# BlueSunOFP.net
KiCad netlist of a schematic drawn in EAGLE
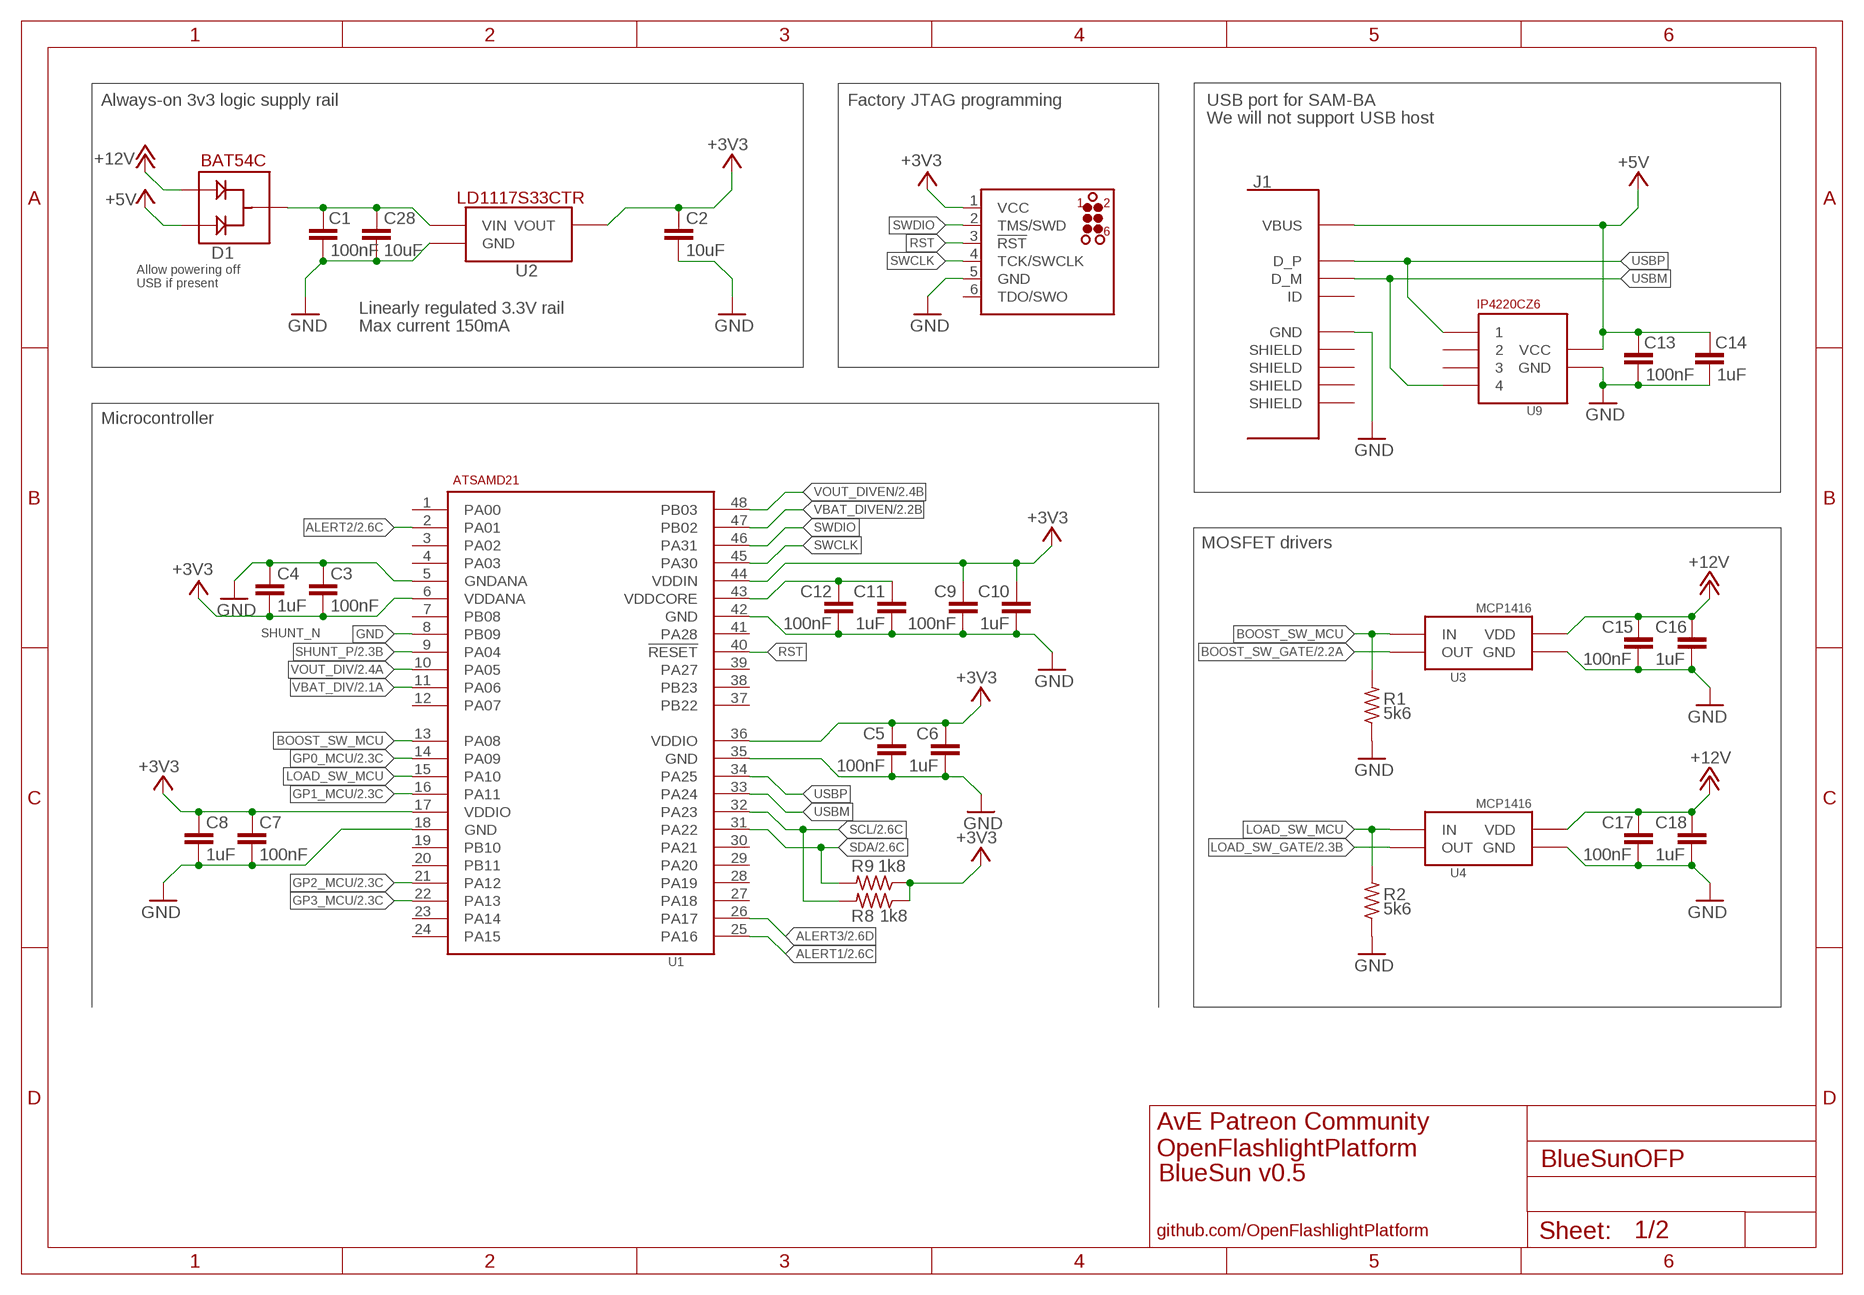
[diagram p0: schematic, sheet 1]
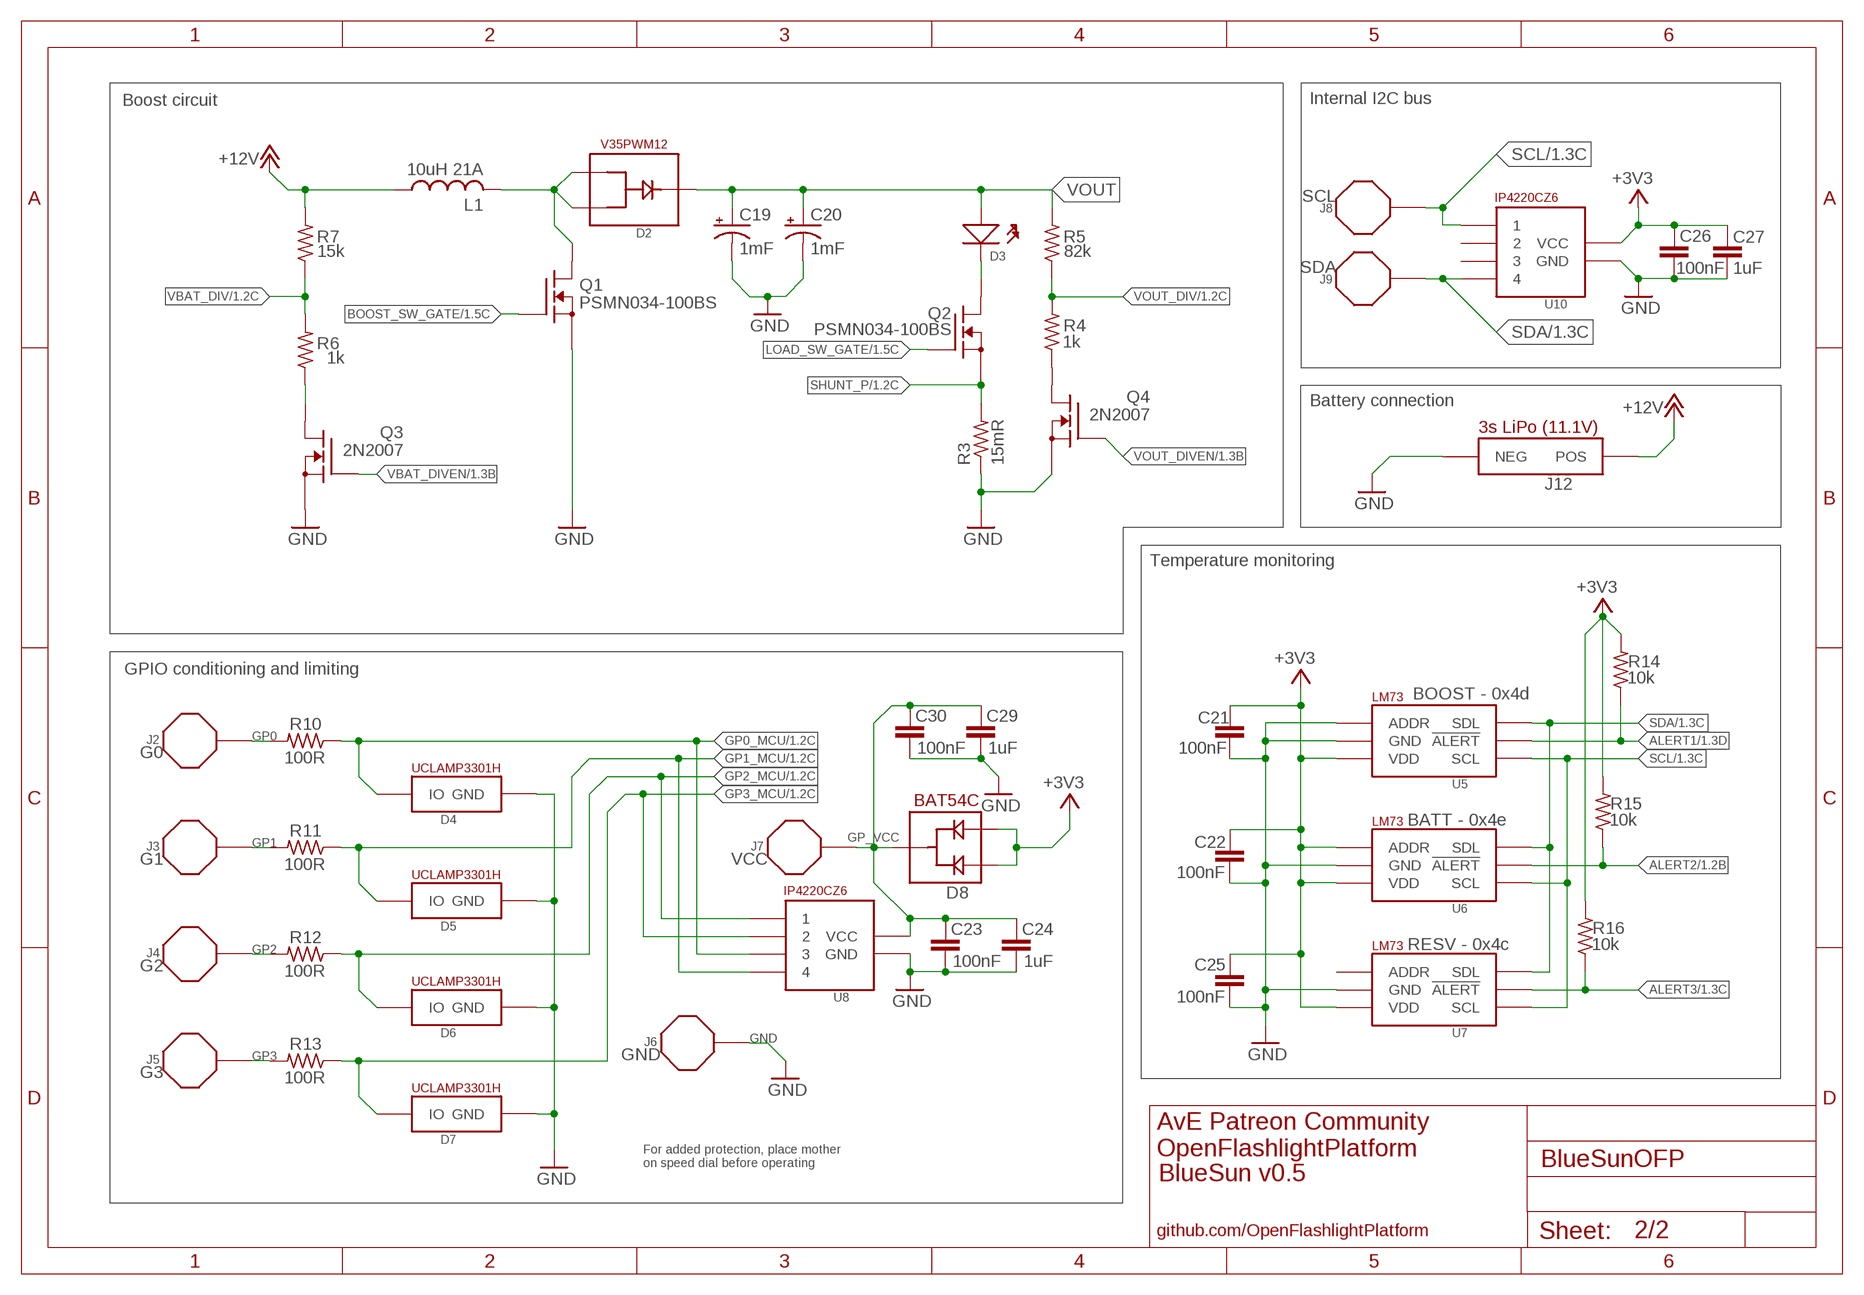
[diagram p1: schematic, sheet 2]

(export (version "E")
  (design (tool "Eeschema 10.0.6"))
  (components
    (comp (ref "C1")
      (value "100nF")
      (footprint "eagle-import:C0603K")
      (libsource (lib "eagle-import") (part "C-EUC0603K"))
    )
    (comp (ref "C2")
      (value "10uF")
      (footprint "eagle-import:C0603K")
      (libsource (lib "eagle-import") (part "C-EUC0603K"))
    )
    (comp (ref "C3")
      (value "100nF")
      (footprint "eagle-import:C0402K")
      (libsource (lib "eagle-import") (part "C-EUC0402K"))
    )
    (comp (ref "C4")
      (value "1uF")
      (footprint "eagle-import:C0402K")
      (libsource (lib "eagle-import") (part "C-EUC0402K"))
    )
    (comp (ref "C5")
      (value "100nF")
      (footprint "eagle-import:C0402K")
      (libsource (lib "eagle-import") (part "C-EUC0402K"))
    )
    (comp (ref "C6")
      (value "1uF")
      (footprint "eagle-import:C0402K")
      (libsource (lib "eagle-import") (part "C-EUC0402K"))
    )
    (comp (ref "C7")
      (value "100nF")
      (footprint "eagle-import:C0402K")
      (libsource (lib "eagle-import") (part "C-EUC0402K"))
    )
    (comp (ref "C8")
      (value "1uF")
      (footprint "eagle-import:C0402K")
      (libsource (lib "eagle-import") (part "C-EUC0402K"))
    )
    (comp (ref "C9")
      (value "100nF")
      (footprint "eagle-import:C0402K")
      (libsource (lib "eagle-import") (part "C-EUC0402K"))
    )
    (comp (ref "C10")
      (value "1uF")
      (footprint "eagle-import:C0402K")
      (libsource (lib "eagle-import") (part "C-EUC0402K"))
    )
    (comp (ref "C11")
      (value "1uF")
      (footprint "eagle-import:C0402K")
      (libsource (lib "eagle-import") (part "C-EUC0402K"))
    )
    (comp (ref "C12")
      (value "100nF")
      (footprint "eagle-import:C0402K")
      (libsource (lib "eagle-import") (part "C-EUC0402K"))
    )
    (comp (ref "C13")
      (value "100nF")
      (footprint "eagle-import:C0603K")
      (libsource (lib "eagle-import") (part "C-EUC0603K"))
    )
    (comp (ref "C14")
      (value "1uF")
      (footprint "eagle-import:C0603K")
      (libsource (lib "eagle-import") (part "C-EUC0603K"))
    )
    (comp (ref "C15")
      (value "100nF")
      (footprint "eagle-import:C0603K")
      (libsource (lib "eagle-import") (part "C-EUC0603K"))
    )
    (comp (ref "C16")
      (value "1uF")
      (footprint "eagle-import:C0603K")
      (libsource (lib "eagle-import") (part "C-EUC0603K"))
    )
    (comp (ref "C17")
      (value "100nF")
      (footprint "eagle-import:C0603K")
      (libsource (lib "eagle-import") (part "C-EUC0603K"))
    )
    (comp (ref "C18")
      (value "1uF")
      (footprint "eagle-import:C0603K")
      (libsource (lib "eagle-import") (part "C-EUC0603K"))
    )
    (comp (ref "C28")
      (value "10uF")
      (footprint "eagle-import:C0603K")
      (libsource (lib "eagle-import") (part "C-EUC0603K"))
    )
    (comp (ref "D1")
      (value "BAT54C")
      (footprint "eagle-import:SOT23")
      (libsource (lib "eagle-import") (part "BAT54C"))
    )
    (comp (ref "J1")
      (value "USBSMT")
      (footprint "eagle-import:USB_SMT")
      (libsource (lib "eagle-import") (part "USBSMT"))
    )
    (comp (ref "R1")
      (value "5k6")
      (footprint "eagle-import:R0603")
      (libsource (lib "eagle-import") (part "R-US_R0603"))
    )
    (comp (ref "R2")
      (value "5k6")
      (footprint "eagle-import:R0603")
      (libsource (lib "eagle-import") (part "R-US_R0603"))
    )
    (comp (ref "R8")
      (value "1k8")
      (footprint "eagle-import:R0603")
      (libsource (lib "eagle-import") (part "R-US_R0603"))
    )
    (comp (ref "R9")
      (value "1k8")
      (footprint "eagle-import:R0603")
      (libsource (lib "eagle-import") (part "R-US_R0603"))
    )
    (comp (ref "U$1")
      (value "JLINK_CONNECT")
      (footprint "eagle-import:TC2030-MCP-NL")
      (libsource (lib "eagle-import") (part "JLINK_CONNECT"))
    )
    (comp (ref "U1")
      (value "SAMD21")
      (footprint "eagle-import:TQFP48")
      (libsource (lib "eagle-import") (part "SAMD21"))
    )
    (comp (ref "U2")
      (value "LD1117S33CTR_3V3_REG")
      (footprint "eagle-import:SOT223")
      (libsource (lib "eagle-import") (part "LD1117S33CTR_3V3_REG"))
    )
    (comp (ref "U3")
      (value "MCP1416")
      (footprint "eagle-import:SOT23-5")
      (libsource (lib "eagle-import") (part "MCP1416"))
    )
    (comp (ref "U4")
      (value "MCP1416")
      (footprint "eagle-import:SOT23-5")
      (libsource (lib "eagle-import") (part "MCP1416"))
    )
    (comp (ref "U9")
      (value "IP4220CZ6")
      (footprint "eagle-import:SOT457")
      (libsource (lib "eagle-import") (part "IP4220CZ6"))
    )
    (comp (ref "C19")
      (value "1mF")
      (footprint "eagle-import:10MMCAP")
      (libsource (lib "eagle-import") (part "10MMCAP"))
    )
    (comp (ref "C20")
      (value "1mF")
      (footprint "eagle-import:10MMCAP")
      (libsource (lib "eagle-import") (part "10MMCAP"))
    )
    (comp (ref "C21")
      (value "100nF")
      (footprint "eagle-import:C0603K")
      (libsource (lib "eagle-import") (part "C-EUC0603K"))
    )
    (comp (ref "C22")
      (value "100nF")
      (footprint "eagle-import:C0603K")
      (libsource (lib "eagle-import") (part "C-EUC0603K"))
    )
    (comp (ref "C23")
      (value "100nF")
      (footprint "eagle-import:C0603K")
      (libsource (lib "eagle-import") (part "C-EUC0603K"))
    )
    (comp (ref "C24")
      (value "1uF")
      (footprint "eagle-import:C0603K")
      (libsource (lib "eagle-import") (part "C-EUC0603K"))
    )
    (comp (ref "C25")
      (value "100nF")
      (footprint "eagle-import:C0603K")
      (libsource (lib "eagle-import") (part "C-EUC0603K"))
    )
    (comp (ref "C26")
      (value "100nF")
      (footprint "eagle-import:C0603K")
      (libsource (lib "eagle-import") (part "C-EUC0603K"))
    )
    (comp (ref "C27")
      (value "1uF")
      (footprint "eagle-import:C0603K")
      (libsource (lib "eagle-import") (part "C-EUC0603K"))
    )
    (comp (ref "C29")
      (value "1uF")
      (footprint "eagle-import:C0603K")
      (libsource (lib "eagle-import") (part "C-EUC0603K"))
    )
    (comp (ref "C30")
      (value "100nF")
      (footprint "eagle-import:C0603K")
      (libsource (lib "eagle-import") (part "C-EUC0603K"))
    )
    (comp (ref "D2")
      (value "DIODE")
      (footprint "eagle-import:SLIMPAK")
      (libsource (lib "eagle-import") (part "DIODE"))
    )
    (comp (ref "D3")
      (value "CREE_COB")
      (footprint "eagle-import:CREE_WIRE_MOUNT")
      (libsource (lib "eagle-import") (part "CREE_COB"))
    )
    (comp (ref "D4")
      (value "UCLAMP3301H")
      (footprint "eagle-import:SOD523")
      (libsource (lib "eagle-import") (part "UCLAMP3301H"))
    )
    (comp (ref "D5")
      (value "UCLAMP3301H")
      (footprint "eagle-import:SOD523")
      (libsource (lib "eagle-import") (part "UCLAMP3301H"))
    )
    (comp (ref "D6")
      (value "UCLAMP3301H")
      (footprint "eagle-import:SOD523")
      (libsource (lib "eagle-import") (part "UCLAMP3301H"))
    )
    (comp (ref "D7")
      (value "UCLAMP3301H")
      (footprint "eagle-import:SOD523")
      (libsource (lib "eagle-import") (part "UCLAMP3301H"))
    )
    (comp (ref "D8")
      (value "BAT54C")
      (footprint "eagle-import:SOT23")
      (libsource (lib "eagle-import") (part "BAT54C"))
    )
    (comp (ref "J2")
      (value "G0")
      (footprint "eagle-import:EXT_PIN")
      (libsource (lib "eagle-import") (part "EXT_PIN"))
    )
    (comp (ref "J3")
      (value "G1")
      (footprint "eagle-import:EXT_PIN")
      (libsource (lib "eagle-import") (part "EXT_PIN"))
    )
    (comp (ref "J4")
      (value "G2")
      (footprint "eagle-import:EXT_PIN")
      (libsource (lib "eagle-import") (part "EXT_PIN"))
    )
    (comp (ref "J5")
      (value "G3")
      (footprint "eagle-import:EXT_PIN")
      (libsource (lib "eagle-import") (part "EXT_PIN"))
    )
    (comp (ref "J6")
      (value "GND")
      (footprint "eagle-import:EXT_PIN")
      (libsource (lib "eagle-import") (part "EXT_PIN"))
    )
    (comp (ref "J7")
      (value "VCC")
      (footprint "eagle-import:EXT_PIN")
      (libsource (lib "eagle-import") (part "EXT_PIN"))
    )
    (comp (ref "J8")
      (value "SCL")
      (footprint "eagle-import:EXT_PIN")
      (libsource (lib "eagle-import") (part "EXT_PIN"))
    )
    (comp (ref "J9")
      (value "SDA")
      (footprint "eagle-import:EXT_PIN")
      (libsource (lib "eagle-import") (part "EXT_PIN"))
    )
    (comp (ref "J12")
      (value "BATTERY")
      (footprint "eagle-import:CREE_WIRE_MOUNT")
      (libsource (lib "eagle-import") (part "BATTERY"))
    )
    (comp (ref "L1")
      (value "10uH 21A")
      (footprint "eagle-import:INDUCTOR")
      (libsource (lib "eagle-import") (part "INDUCTOR"))
    )
    (comp (ref "Q1")
      (value "PSMN034-100BS")
      (footprint "eagle-import:D2PAK")
      (libsource (lib "eagle-import") (part "MOSFET"))
    )
    (comp (ref "Q2")
      (value "PSMN034-100BS")
      (footprint "eagle-import:D2PAK")
      (libsource (lib "eagle-import") (part "MOSFET"))
    )
    (comp (ref "Q3")
      (value "2N2007")
      (footprint "eagle-import:SOT23")
      (libsource (lib "eagle-import") (part "SMALL_MOSFET"))
    )
    (comp (ref "Q4")
      (value "2N2007")
      (footprint "eagle-import:SOT23")
      (libsource (lib "eagle-import") (part "SMALL_MOSFET"))
    )
    (comp (ref "R3")
      (value "15mR")
      (footprint "eagle-import:R2512")
      (libsource (lib "eagle-import") (part "R-US_R2512"))
    )
    (comp (ref "R4")
      (value "1k")
      (footprint "eagle-import:R0603")
      (libsource (lib "eagle-import") (part "R-US_R0603"))
    )
    (comp (ref "R5")
      (value "82k")
      (footprint "eagle-import:R0603")
      (libsource (lib "eagle-import") (part "R-US_R0603"))
    )
    (comp (ref "R6")
      (value "1k")
      (footprint "eagle-import:R0603")
      (libsource (lib "eagle-import") (part "R-US_R0603"))
    )
    (comp (ref "R7")
      (value "15k")
      (footprint "eagle-import:R0603")
      (libsource (lib "eagle-import") (part "R-US_R0603"))
    )
    (comp (ref "R10")
      (value "100R")
      (footprint "eagle-import:R0603")
      (libsource (lib "eagle-import") (part "R-US_R0603"))
    )
    (comp (ref "R11")
      (value "100R")
      (footprint "eagle-import:R0603")
      (libsource (lib "eagle-import") (part "R-US_R0603"))
    )
    (comp (ref "R12")
      (value "100R")
      (footprint "eagle-import:R0603")
      (libsource (lib "eagle-import") (part "R-US_R0603"))
    )
    (comp (ref "R13")
      (value "100R")
      (footprint "eagle-import:R0603")
      (libsource (lib "eagle-import") (part "R-US_R0603"))
    )
    (comp (ref "R14")
      (value "10k")
      (footprint "eagle-import:R0603")
      (libsource (lib "eagle-import") (part "R-US_R0603"))
    )
    (comp (ref "R15")
      (value "10k")
      (footprint "eagle-import:R0603")
      (libsource (lib "eagle-import") (part "R-US_R0603"))
    )
    (comp (ref "R16")
      (value "10k")
      (footprint "eagle-import:R0603")
      (libsource (lib "eagle-import") (part "R-US_R0603"))
    )
    (comp (ref "U5")
      (value "LM73")
      (footprint "eagle-import:SOT23-6")
      (libsource (lib "eagle-import") (part "LM73"))
    )
    (comp (ref "U6")
      (value "LM73")
      (footprint "eagle-import:SOT23-6")
      (libsource (lib "eagle-import") (part "LM73"))
    )
    (comp (ref "U7")
      (value "LM73")
      (footprint "eagle-import:SOT23-6")
      (libsource (lib "eagle-import") (part "LM73"))
    )
    (comp (ref "U8")
      (value "IP4220CZ6")
      (footprint "eagle-import:SOT457")
      (libsource (lib "eagle-import") (part "IP4220CZ6"))
    )
    (comp (ref "U10")
      (value "IP4220CZ6")
      (footprint "eagle-import:SOT457")
      (libsource (lib "eagle-import") (part "IP4220CZ6"))
    )
  )
  (nets
    (net (code "1") (name "+3V3") (class "Default")
      (node (ref "C10") (pin "1") (pinfunction "1_1") (pintype "passive"))
      (node (ref "C2") (pin "1") (pinfunction "1_1") (pintype "passive"))
      (node (ref "C21") (pin "1") (pinfunction "1_1") (pintype "passive"))
      (node (ref "C22") (pin "1") (pinfunction "1_1") (pintype "passive"))
      (node (ref "C25") (pin "1") (pinfunction "1_1") (pintype "passive"))
      (node (ref "C26") (pin "1") (pinfunction "1_1") (pintype "passive"))
      (node (ref "C27") (pin "1") (pinfunction "1_1") (pintype "passive"))
      (node (ref "C3") (pin "2") (pinfunction "2_2") (pintype "passive"))
      (node (ref "C4") (pin "2") (pinfunction "2_2") (pintype "passive"))
      (node (ref "C5") (pin "1") (pinfunction "1_1") (pintype "passive"))
      (node (ref "C6") (pin "1") (pinfunction "1_1") (pintype "passive"))
      (node (ref "C7") (pin "1") (pinfunction "1_1") (pintype "passive"))
      (node (ref "C8") (pin "1") (pinfunction "1_1") (pintype "passive"))
      (node (ref "C9") (pin "1") (pinfunction "1_1") (pintype "passive"))
      (node (ref "D8") (pin "1") (pinfunction "P1_1") (pintype "bidirectional"))
      (node (ref "D8") (pin "2") (pinfunction "P2_2") (pintype "bidirectional"))
      (node (ref "R14") (pin "2") (pinfunction "2_2") (pintype "passive"))
      (node (ref "R15") (pin "2") (pinfunction "2_2") (pintype "passive"))
      (node (ref "R16") (pin "2") (pinfunction "2_2") (pintype "passive"))
      (node (ref "R8") (pin "1") (pinfunction "1_1") (pintype "passive"))
      (node (ref "R9") (pin "1") (pinfunction "1_1") (pintype "passive"))
      (node (ref "U$1") (pin "1") (pinfunction "VCC_1") (pintype "passive"))
      (node (ref "U1") (pin "17") (pinfunction "VDDIO_17") (pintype "bidirectional"))
      (node (ref "U1") (pin "36") (pinfunction "VDDIO_36") (pintype "bidirectional"))
      (node (ref "U1") (pin "44") (pinfunction "VDDIN_44") (pintype "bidirectional"))
      (node (ref "U1") (pin "6") (pinfunction "VDDANA_6") (pintype "bidirectional"))
      (node (ref "U10") (pin "5") (pinfunction "VCC_5") (pintype "bidirectional"))
      (node (ref "U2") (pin "2") (pinfunction "VOUT_2") (pintype "bidirectional"))
      (node (ref "U5") (pin "3") (pinfunction "VDD_3") (pintype "bidirectional"))
      (node (ref "U6") (pin "1") (pinfunction "ADDR_1") (pintype "bidirectional"))
      (node (ref "U6") (pin "3") (pinfunction "VDD_3") (pintype "bidirectional"))
      (node (ref "U7") (pin "3") (pinfunction "VDD_3") (pintype "bidirectional"))
    )
    (net (code "2") (name "+5V") (class "Default")
      (node (ref "C13") (pin "1") (pinfunction "1_1") (pintype "passive"))
      (node (ref "C14") (pin "1") (pinfunction "1_1") (pintype "passive"))
      (node (ref "D1") (pin "2") (pinfunction "P2_2") (pintype "bidirectional"))
      (node (ref "J1") (pin "1VBUS") (pinfunction "VBUS_1VBUS") (pintype "bidirectional"))
      (node (ref "U9") (pin "5") (pinfunction "VCC_5") (pintype "bidirectional"))
    )
    (net (code "3") (name "+12V") (class "Default")
      (node (ref "C15") (pin "1") (pinfunction "1_1") (pintype "passive"))
      (node (ref "C16") (pin "1") (pinfunction "1_1") (pintype "passive"))
      (node (ref "C17") (pin "1") (pinfunction "1_1") (pintype "passive"))
      (node (ref "C18") (pin "1") (pinfunction "1_1") (pintype "passive"))
      (node (ref "D1") (pin "1") (pinfunction "P1_1") (pintype "bidirectional"))
      (node (ref "J12") (pin "POS") (pinfunction "POS_POS") (pintype "bidirectional"))
      (node (ref "L1") (pin "P$1") (pinfunction "1_P$1") (pintype "passive"))
      (node (ref "R7") (pin "2") (pinfunction "2_2") (pintype "passive"))
      (node (ref "U3") (pin "2") (pinfunction "VDD_2") (pintype "bidirectional"))
      (node (ref "U4") (pin "2") (pinfunction "VDD_2") (pintype "bidirectional"))
    )
    (net (code "4") (name "ALERT1") (class "Default")
      (node (ref "R14") (pin "1") (pinfunction "1_1") (pintype "passive"))
      (node (ref "U1") (pin "25") (pinfunction "PA16_25") (pintype "bidirectional"))
      (node (ref "U5") (pin "5") (pinfunction "~{ALERT}_5") (pintype "bidirectional"))
    )
    (net (code "5") (name "ALERT2") (class "Default")
      (node (ref "R15") (pin "1") (pinfunction "1_1") (pintype "passive"))
      (node (ref "U1") (pin "2") (pinfunction "PA01_2") (pintype "bidirectional"))
      (node (ref "U6") (pin "5") (pinfunction "~{ALERT}_5") (pintype "bidirectional"))
    )
    (net (code "6") (name "ALERT3") (class "Default")
      (node (ref "R16") (pin "1") (pinfunction "1_1") (pintype "passive"))
      (node (ref "U1") (pin "26") (pinfunction "PA17_26") (pintype "bidirectional"))
      (node (ref "U7") (pin "5") (pinfunction "~{ALERT}_5") (pintype "bidirectional"))
    )
    (net (code "7") (name "BOOST_SW_GATE") (class "Default")
      (node (ref "Q1") (pin "1") (pinfunction "G_1") (pintype "passive"))
      (node (ref "U3") (pin "5") (pinfunction "OUT_5") (pintype "bidirectional"))
    )
    (net (code "8") (name "BOOST_SW_MCU") (class "Default")
      (node (ref "R1") (pin "2") (pinfunction "2_2") (pintype "passive"))
      (node (ref "U1") (pin "13") (pinfunction "PA08_13") (pintype "bidirectional"))
      (node (ref "U3") (pin "3") (pinfunction "IN_3") (pintype "bidirectional"))
    )
    (net (code "9") (name "GND") (class "Default")
      (node (ref "C1") (pin "2") (pinfunction "2_2") (pintype "passive"))
      (node (ref "C10") (pin "2") (pinfunction "2_2") (pintype "passive"))
      (node (ref "C11") (pin "2") (pinfunction "2_2") (pintype "passive"))
      (node (ref "C12") (pin "2") (pinfunction "2_2") (pintype "passive"))
      (node (ref "C13") (pin "2") (pinfunction "2_2") (pintype "passive"))
      (node (ref "C14") (pin "2") (pinfunction "2_2") (pintype "passive"))
      (node (ref "C15") (pin "2") (pinfunction "2_2") (pintype "passive"))
      (node (ref "C16") (pin "2") (pinfunction "2_2") (pintype "passive"))
      (node (ref "C17") (pin "2") (pinfunction "2_2") (pintype "passive"))
      (node (ref "C18") (pin "2") (pinfunction "2_2") (pintype "passive"))
      (node (ref "C19") (pin "NEG") (pinfunction "-_NEG") (pintype "passive"))
      (node (ref "C2") (pin "2") (pinfunction "2_2") (pintype "passive"))
      (node (ref "C20") (pin "NEG") (pinfunction "-_NEG") (pintype "passive"))
      (node (ref "C21") (pin "2") (pinfunction "2_2") (pintype "passive"))
      (node (ref "C22") (pin "2") (pinfunction "2_2") (pintype "passive"))
      (node (ref "C23") (pin "2") (pinfunction "2_2") (pintype "passive"))
      (node (ref "C24") (pin "2") (pinfunction "2_2") (pintype "passive"))
      (node (ref "C25") (pin "2") (pinfunction "2_2") (pintype "passive"))
      (node (ref "C26") (pin "2") (pinfunction "2_2") (pintype "passive"))
      (node (ref "C27") (pin "2") (pinfunction "2_2") (pintype "passive"))
      (node (ref "C28") (pin "2") (pinfunction "2_2") (pintype "passive"))
      (node (ref "C29") (pin "2") (pinfunction "2_2") (pintype "passive"))
      (node (ref "C3") (pin "1") (pinfunction "1_1") (pintype "passive"))
      (node (ref "C30") (pin "2") (pinfunction "2_2") (pintype "passive"))
      (node (ref "C4") (pin "1") (pinfunction "1_1") (pintype "passive"))
      (node (ref "C5") (pin "2") (pinfunction "2_2") (pintype "passive"))
      (node (ref "C6") (pin "2") (pinfunction "2_2") (pintype "passive"))
      (node (ref "C7") (pin "2") (pinfunction "2_2") (pintype "passive"))
      (node (ref "C8") (pin "2") (pinfunction "2_2") (pintype "passive"))
      (node (ref "C9") (pin "2") (pinfunction "2_2") (pintype "passive"))
      (node (ref "D4") (pin "NOLINE") (pinfunction "GND_NOLINE") (pintype "bidirectional"))
      (node (ref "D5") (pin "NOLINE") (pinfunction "GND_NOLINE") (pintype "bidirectional"))
      (node (ref "D6") (pin "NOLINE") (pinfunction "GND_NOLINE") (pintype "bidirectional"))
      (node (ref "D7") (pin "NOLINE") (pinfunction "GND_NOLINE") (pintype "bidirectional"))
      (node (ref "J1") (pin "5GND") (pinfunction "GND_5GND") (pintype "bidirectional"))
      (node (ref "J12") (pin "NEG") (pinfunction "NEG_NEG") (pintype "bidirectional"))
      (node (ref "J6") (pin "P$1") (pinfunction "P$1_P$1") (pintype "bidirectional"))
      (node (ref "Q1") (pin "3") (pinfunction "S_3") (pintype "passive"))
      (node (ref "Q3") (pin "2") (pinfunction "S_2") (pintype "passive"))
      (node (ref "Q4") (pin "2") (pinfunction "S_2") (pintype "passive"))
      (node (ref "R1") (pin "1") (pinfunction "1_1") (pintype "passive"))
      (node (ref "R2") (pin "1") (pinfunction "1_1") (pintype "passive"))
      (node (ref "R3") (pin "1") (pinfunction "1_1") (pintype "passive"))
      (node (ref "U$1") (pin "5") (pinfunction "GND_5") (pintype "power_in"))
      (node (ref "U1") (pin "18") (pinfunction "GND_18") (pintype "bidirectional"))
      (node (ref "U1") (pin "35") (pinfunction "GND_35") (pintype "bidirectional"))
      (node (ref "U1") (pin "42") (pinfunction "GND_42") (pintype "bidirectional"))
      (node (ref "U1") (pin "5") (pinfunction "GNDANA_5") (pintype "bidirectional"))
      (node (ref "U1") (pin "8") (pinfunction "PB09_8") (pintype "bidirectional"))
      (node (ref "U10") (pin "2") (pinfunction "GND_2") (pintype "bidirectional"))
      (node (ref "U2") (pin "1") (pinfunction "GND_1") (pintype "bidirectional"))
      (node (ref "U3") (pin "4") (pinfunction "GND_4") (pintype "bidirectional"))
      (node (ref "U4") (pin "4") (pinfunction "GND_4") (pintype "bidirectional"))
      (node (ref "U5") (pin "1") (pinfunction "ADDR_1") (pintype "bidirectional"))
      (node (ref "U5") (pin "2") (pinfunction "GND_2") (pintype "bidirectional"))
      (node (ref "U6") (pin "2") (pinfunction "GND_2") (pintype "bidirectional"))
      (node (ref "U7") (pin "2") (pinfunction "GND_2") (pintype "bidirectional"))
      (node (ref "U8") (pin "2") (pinfunction "GND_2") (pintype "bidirectional"))
      (node (ref "U9") (pin "2") (pinfunction "GND_2") (pintype "bidirectional"))
    )
    (net (code "10") (name "GP0") (class "Default")
      (node (ref "J2") (pin "P$1") (pinfunction "P$1_P$1") (pintype "bidirectional"))
      (node (ref "R10") (pin "2") (pinfunction "2_2") (pintype "passive"))
    )
    (net (code "11") (name "GP0_MCU") (class "Default")
      (node (ref "D4") (pin "LINE") (pinfunction "IO_LINE") (pintype "bidirectional"))
      (node (ref "R10") (pin "1") (pinfunction "1_1") (pintype "passive"))
      (node (ref "U1") (pin "14") (pinfunction "PA09_14") (pintype "bidirectional"))
      (node (ref "U8") (pin "4") (pinfunction "3_4") (pintype "bidirectional"))
    )
    (net (code "12") (name "GP1") (class "Default")
      (node (ref "J3") (pin "P$1") (pinfunction "P$1_P$1") (pintype "bidirectional"))
      (node (ref "R11") (pin "2") (pinfunction "2_2") (pintype "passive"))
    )
    (net (code "13") (name "GP1_MCU") (class "Default")
      (node (ref "D5") (pin "LINE") (pinfunction "IO_LINE") (pintype "bidirectional"))
      (node (ref "R11") (pin "1") (pinfunction "1_1") (pintype "passive"))
      (node (ref "U1") (pin "16") (pinfunction "PA11_16") (pintype "bidirectional"))
      (node (ref "U8") (pin "6") (pinfunction "4_6") (pintype "bidirectional"))
    )
    (net (code "14") (name "GP2") (class "Default")
      (node (ref "J4") (pin "P$1") (pinfunction "P$1_P$1") (pintype "bidirectional"))
      (node (ref "R12") (pin "2") (pinfunction "2_2") (pintype "passive"))
    )
    (net (code "15") (name "GP2_MCU") (class "Default")
      (node (ref "D6") (pin "LINE") (pinfunction "IO_LINE") (pintype "bidirectional"))
      (node (ref "R12") (pin "1") (pinfunction "1_1") (pintype "passive"))
      (node (ref "U1") (pin "21") (pinfunction "PA12_21") (pintype "bidirectional"))
      (node (ref "U8") (pin "1") (pinfunction "1_1") (pintype "bidirectional"))
    )
    (net (code "16") (name "GP3") (class "Default")
      (node (ref "J5") (pin "P$1") (pinfunction "P$1_P$1") (pintype "bidirectional"))
      (node (ref "R13") (pin "2") (pinfunction "2_2") (pintype "passive"))
    )
    (net (code "17") (name "GP3_MCU") (class "Default")
      (node (ref "D7") (pin "LINE") (pinfunction "IO_LINE") (pintype "bidirectional"))
      (node (ref "R13") (pin "1") (pinfunction "1_1") (pintype "passive"))
      (node (ref "U1") (pin "22") (pinfunction "PA13_22") (pintype "bidirectional"))
      (node (ref "U8") (pin "3") (pinfunction "2_3") (pintype "bidirectional"))
    )
    (net (code "18") (name "GP_VCC") (class "Default")
      (node (ref "C23") (pin "1") (pinfunction "1_1") (pintype "passive"))
      (node (ref "C24") (pin "1") (pinfunction "1_1") (pintype "passive"))
      (node (ref "C29") (pin "1") (pinfunction "1_1") (pintype "passive"))
      (node (ref "C30") (pin "1") (pinfunction "1_1") (pintype "passive"))
      (node (ref "D8") (pin "3") (pinfunction "NEG_3") (pintype "bidirectional"))
      (node (ref "J7") (pin "P$1") (pinfunction "P$1_P$1") (pintype "bidirectional"))
      (node (ref "U8") (pin "5") (pinfunction "VCC_5") (pintype "bidirectional"))
    )
    (net (code "19") (name "LOAD_SW_GATE") (class "Default")
      (node (ref "Q2") (pin "1") (pinfunction "G_1") (pintype "passive"))
      (node (ref "U4") (pin "5") (pinfunction "OUT_5") (pintype "bidirectional"))
    )
    (net (code "20") (name "LOAD_SW_MCU") (class "Default")
      (node (ref "R2") (pin "2") (pinfunction "2_2") (pintype "passive"))
      (node (ref "U1") (pin "15") (pinfunction "PA10_15") (pintype "bidirectional"))
      (node (ref "U4") (pin "3") (pinfunction "IN_3") (pintype "bidirectional"))
    )
    (net (code "21") (name "Net-(D1-NEG)") (class "Default")
      (node (ref "C1") (pin "1") (pinfunction "1_1") (pintype "passive"))
      (node (ref "C28") (pin "1") (pinfunction "1_1") (pintype "passive"))
      (node (ref "D1") (pin "3") (pinfunction "NEG_3") (pintype "bidirectional"))
      (node (ref "U2") (pin "3") (pinfunction "VIN_3") (pintype "bidirectional"))
    )
    (net (code "22") (name "Net-(L1-2)") (class "Default")
      (node (ref "D2") (pin "1") (pinfunction "1_1") (pintype "bidirectional"))
      (node (ref "D2") (pin "2") (pinfunction "2_2") (pintype "bidirectional"))
      (node (ref "L1") (pin "P$2") (pinfunction "2_P$2") (pintype "passive"))
      (node (ref "Q1") (pin "2") (pinfunction "D_2") (pintype "passive"))
    )
    (net (code "23") (name "Net-(Q2-D)") (class "Default")
      (node (ref "D3") (pin "NEG") (pinfunction "NEG_NEG") (pintype "bidirectional"))
      (node (ref "Q2") (pin "2") (pinfunction "D_2") (pintype "passive"))
    )
    (net (code "24") (name "Net-(Q3-D)") (class "Default")
      (node (ref "Q3") (pin "3") (pinfunction "D_3") (pintype "passive"))
      (node (ref "R6") (pin "1") (pinfunction "1_1") (pintype "passive"))
    )
    (net (code "25") (name "Net-(Q4-D)") (class "Default")
      (node (ref "Q4") (pin "3") (pinfunction "D_3") (pintype "passive"))
      (node (ref "R4") (pin "1") (pinfunction "1_1") (pintype "passive"))
    )
    (net (code "26") (name "Net-(U1-VDDCORE)") (class "Default")
      (node (ref "C11") (pin "1") (pinfunction "1_1") (pintype "passive"))
      (node (ref "C12") (pin "1") (pinfunction "1_1") (pintype "passive"))
      (node (ref "U1") (pin "43") (pinfunction "VDDCORE_43") (pintype "bidirectional"))
    )
    (net (code "27") (name "RST") (class "Default")
      (node (ref "U$1") (pin "3") (pinfunction "~{RST}_3") (pintype "bidirectional"))
      (node (ref "U1") (pin "40") (pinfunction "~{RESET}_40") (pintype "bidirectional"))
    )
    (net (code "28") (name "SCL") (class "Default")
      (node (ref "J8") (pin "P$1") (pinfunction "P$1_P$1") (pintype "bidirectional"))
      (node (ref "R8") (pin "2") (pinfunction "2_2") (pintype "passive"))
      (node (ref "U1") (pin "32") (pinfunction "PA23_32") (pintype "bidirectional"))
      (node (ref "U10") (pin "1") (pinfunction "1_1") (pintype "bidirectional"))
      (node (ref "U5") (pin "4") (pinfunction "SCL_4") (pintype "bidirectional"))
      (node (ref "U6") (pin "4") (pinfunction "SCL_4") (pintype "bidirectional"))
      (node (ref "U7") (pin "4") (pinfunction "SCL_4") (pintype "bidirectional"))
    )
    (net (code "29") (name "SDA") (class "Default")
      (node (ref "J9") (pin "P$1") (pinfunction "P$1_P$1") (pintype "bidirectional"))
      (node (ref "R9") (pin "2") (pinfunction "2_2") (pintype "passive"))
      (node (ref "U1") (pin "31") (pinfunction "PA22_31") (pintype "bidirectional"))
      (node (ref "U10") (pin "6") (pinfunction "4_6") (pintype "bidirectional"))
      (node (ref "U5") (pin "6") (pinfunction "SDL_6") (pintype "bidirectional"))
      (node (ref "U6") (pin "6") (pinfunction "SDL_6") (pintype "bidirectional"))
      (node (ref "U7") (pin "6") (pinfunction "SDL_6") (pintype "bidirectional"))
    )
    (net (code "30") (name "SHUNT_P") (class "Default")
      (node (ref "Q2") (pin "3") (pinfunction "S_3") (pintype "passive"))
      (node (ref "R3") (pin "2") (pinfunction "2_2") (pintype "passive"))
      (node (ref "U1") (pin "9") (pinfunction "PA04_9") (pintype "bidirectional"))
    )
    (net (code "31") (name "SWCLK") (class "Default")
      (node (ref "U$1") (pin "4") (pinfunction "TCK/SWCLK_4") (pintype "bidirectional"))
      (node (ref "U1") (pin "45") (pinfunction "PA30_45") (pintype "bidirectional"))
    )
    (net (code "32") (name "SWDIO") (class "Default")
      (node (ref "U$1") (pin "2") (pinfunction "TMS/SWD_2") (pintype "bidirectional"))
      (node (ref "U1") (pin "46") (pinfunction "PA31_46") (pintype "bidirectional"))
    )
    (net (code "33") (name "USBM") (class "Default")
      (node (ref "J1") (pin "2D-") (pinfunction "D_M_2D-") (pintype "bidirectional"))
      (node (ref "U1") (pin "33") (pinfunction "PA24_33") (pintype "bidirectional"))
      (node (ref "U9") (pin "6") (pinfunction "4_6") (pintype "bidirectional"))
    )
    (net (code "34") (name "USBP") (class "Default")
      (node (ref "J1") (pin "3D+") (pinfunction "D_P_3D+") (pintype "bidirectional"))
      (node (ref "U1") (pin "34") (pinfunction "PA25_34") (pintype "bidirectional"))
      (node (ref "U9") (pin "1") (pinfunction "1_1") (pintype "bidirectional"))
    )
    (net (code "35") (name "VBAT_DIV") (class "Default")
      (node (ref "R6") (pin "2") (pinfunction "2_2") (pintype "passive"))
      (node (ref "R7") (pin "1") (pinfunction "1_1") (pintype "passive"))
      (node (ref "U1") (pin "11") (pinfunction "PA06_11") (pintype "bidirectional"))
    )
    (net (code "36") (name "VBAT_DIVEN") (class "Default")
      (node (ref "Q3") (pin "1") (pinfunction "G_1") (pintype "passive"))
      (node (ref "U1") (pin "47") (pinfunction "PB02_47") (pintype "bidirectional"))
    )
    (net (code "37") (name "VOUT") (class "Default")
      (node (ref "C19") (pin "POS") (pinfunction "+_POS") (pintype "passive"))
      (node (ref "C20") (pin "POS") (pinfunction "+_POS") (pintype "passive"))
      (node (ref "D2") (pin "K") (pinfunction "K_K") (pintype "bidirectional"))
      (node (ref "D3") (pin "POS") (pinfunction "POS_POS") (pintype "bidirectional"))
      (node (ref "R5") (pin "2") (pinfunction "2_2") (pintype "passive"))
    )
    (net (code "38") (name "VOUT_DIV") (class "Default")
      (node (ref "R4") (pin "2") (pinfunction "2_2") (pintype "passive"))
      (node (ref "R5") (pin "1") (pinfunction "1_1") (pintype "passive"))
      (node (ref "U1") (pin "10") (pinfunction "PA05_10") (pintype "bidirectional"))
    )
    (net (code "39") (name "VOUT_DIVEN") (class "Default")
      (node (ref "Q4") (pin "1") (pinfunction "G_1") (pintype "passive"))
      (node (ref "U1") (pin "48") (pinfunction "PB03_48") (pintype "bidirectional"))
    )
    (net (code "40") (name "unconnected-(J1-ID-Pad4ID)") (class "Default")
      (node (ref "J1") (pin "4ID") (pinfunction "ID_4ID") (pintype "bidirectional"))
    )
    (net (code "41") (name "unconnected-(J1-SHIELD-PadSHIELD@1)") (class "Default")
      (node (ref "J1") (pin "SHIELD@1") (pinfunction "SHIELD_SHIELD@1") (pintype "no_connect"))
    )
    (net (code "42") (name "unconnected-(J1-SHIELD-PadSHIELD@2)") (class "Default")
      (node (ref "J1") (pin "SHIELD@2") (pinfunction "SHIELD_SHIELD@2") (pintype "no_connect"))
    )
    (net (code "43") (name "unconnected-(J1-SHIELD-PadSHIELD@3)") (class "Default")
      (node (ref "J1") (pin "SHIELD@3") (pinfunction "SHIELD_SHIELD@3") (pintype "no_connect"))
    )
    (net (code "44") (name "unconnected-(J1-SHIELD-PadSHIELD@4)") (class "Default")
      (node (ref "J1") (pin "SHIELD@4") (pinfunction "SHIELD_SHIELD@4") (pintype "no_connect"))
    )
    (net (code "45") (name "unconnected-(U$1-TDO{slash}SWO-Pad6)") (class "Default")
      (node (ref "U$1") (pin "6") (pinfunction "TDO/SWO_6") (pintype "bidirectional"))
    )
    (net (code "46") (name "unconnected-(U1-PA00-Pad1)") (class "Default")
      (node (ref "U1") (pin "1") (pinfunction "PA00_1") (pintype "bidirectional"))
    )
    (net (code "47") (name "unconnected-(U1-PA02-Pad3)") (class "Default")
      (node (ref "U1") (pin "3") (pinfunction "PA02_3") (pintype "bidirectional"))
    )
    (net (code "48") (name "unconnected-(U1-PA03-Pad4)") (class "Default")
      (node (ref "U1") (pin "4") (pinfunction "PA03_4") (pintype "bidirectional"))
    )
    (net (code "49") (name "unconnected-(U1-PA07-Pad12)") (class "Default")
      (node (ref "U1") (pin "12") (pinfunction "PA07_12") (pintype "bidirectional"))
    )
    (net (code "50") (name "unconnected-(U1-PA14-Pad23)") (class "Default")
      (node (ref "U1") (pin "23") (pinfunction "PA14_23") (pintype "bidirectional"))
    )
    (net (code "51") (name "unconnected-(U1-PA15-Pad24)") (class "Default")
      (node (ref "U1") (pin "24") (pinfunction "PA15_24") (pintype "bidirectional"))
    )
    (net (code "52") (name "unconnected-(U1-PA18-Pad27)") (class "Default")
      (node (ref "U1") (pin "27") (pinfunction "PA18_27") (pintype "bidirectional"))
    )
    (net (code "53") (name "unconnected-(U1-PA19-Pad28)") (class "Default")
      (node (ref "U1") (pin "28") (pinfunction "PA19_28") (pintype "bidirectional"))
    )
    (net (code "54") (name "unconnected-(U1-PA20-Pad29)") (class "Default")
      (node (ref "U1") (pin "29") (pinfunction "PA20_29") (pintype "bidirectional"))
    )
    (net (code "55") (name "unconnected-(U1-PA21-Pad30)") (class "Default")
      (node (ref "U1") (pin "30") (pinfunction "PA21_30") (pintype "bidirectional"))
    )
    (net (code "56") (name "unconnected-(U1-PA27-Pad39)") (class "Default")
      (node (ref "U1") (pin "39") (pinfunction "PA27_39") (pintype "bidirectional"))
    )
    (net (code "57") (name "unconnected-(U1-PA28-Pad41)") (class "Default")
      (node (ref "U1") (pin "41") (pinfunction "PA28_41") (pintype "bidirectional"))
    )
    (net (code "58") (name "unconnected-(U1-PB08-Pad7)") (class "Default")
      (node (ref "U1") (pin "7") (pinfunction "PB08_7") (pintype "bidirectional"))
    )
    (net (code "59") (name "unconnected-(U1-PB10-Pad19)") (class "Default")
      (node (ref "U1") (pin "19") (pinfunction "PB10_19") (pintype "bidirectional"))
    )
    (net (code "60") (name "unconnected-(U1-PB11-Pad20)") (class "Default")
      (node (ref "U1") (pin "20") (pinfunction "PB11_20") (pintype "bidirectional"))
    )
    (net (code "61") (name "unconnected-(U1-PB22-Pad37)") (class "Default")
      (node (ref "U1") (pin "37") (pinfunction "PB22_37") (pintype "bidirectional"))
    )
    (net (code "62") (name "unconnected-(U1-PB23-Pad38)") (class "Default")
      (node (ref "U1") (pin "38") (pinfunction "PB23_38") (pintype "bidirectional"))
    )
    (net (code "63") (name "unconnected-(U7-ADDR-Pad1)") (class "Default")
      (node (ref "U7") (pin "1") (pinfunction "ADDR_1") (pintype "bidirectional"))
    )
    (net (code "64") (name "unconnected-(U9-2-Pad3)") (class "Default")
      (node (ref "U9") (pin "3") (pinfunction "2_3") (pintype "bidirectional"))
    )
    (net (code "65") (name "unconnected-(U9-3-Pad4)") (class "Default")
      (node (ref "U9") (pin "4") (pinfunction "3_4") (pintype "bidirectional"))
    )
    (net (code "66") (name "unconnected-(U10-2-Pad3)") (class "Default")
      (node (ref "U10") (pin "3") (pinfunction "2_3") (pintype "bidirectional"))
    )
    (net (code "67") (name "unconnected-(U10-3-Pad4)") (class "Default")
      (node (ref "U10") (pin "4") (pinfunction "3_4") (pintype "bidirectional"))
    )
  )
)
